# mr_radar_ferret_afe.net
KiCad netlist of a schematic drawn in EAGLE
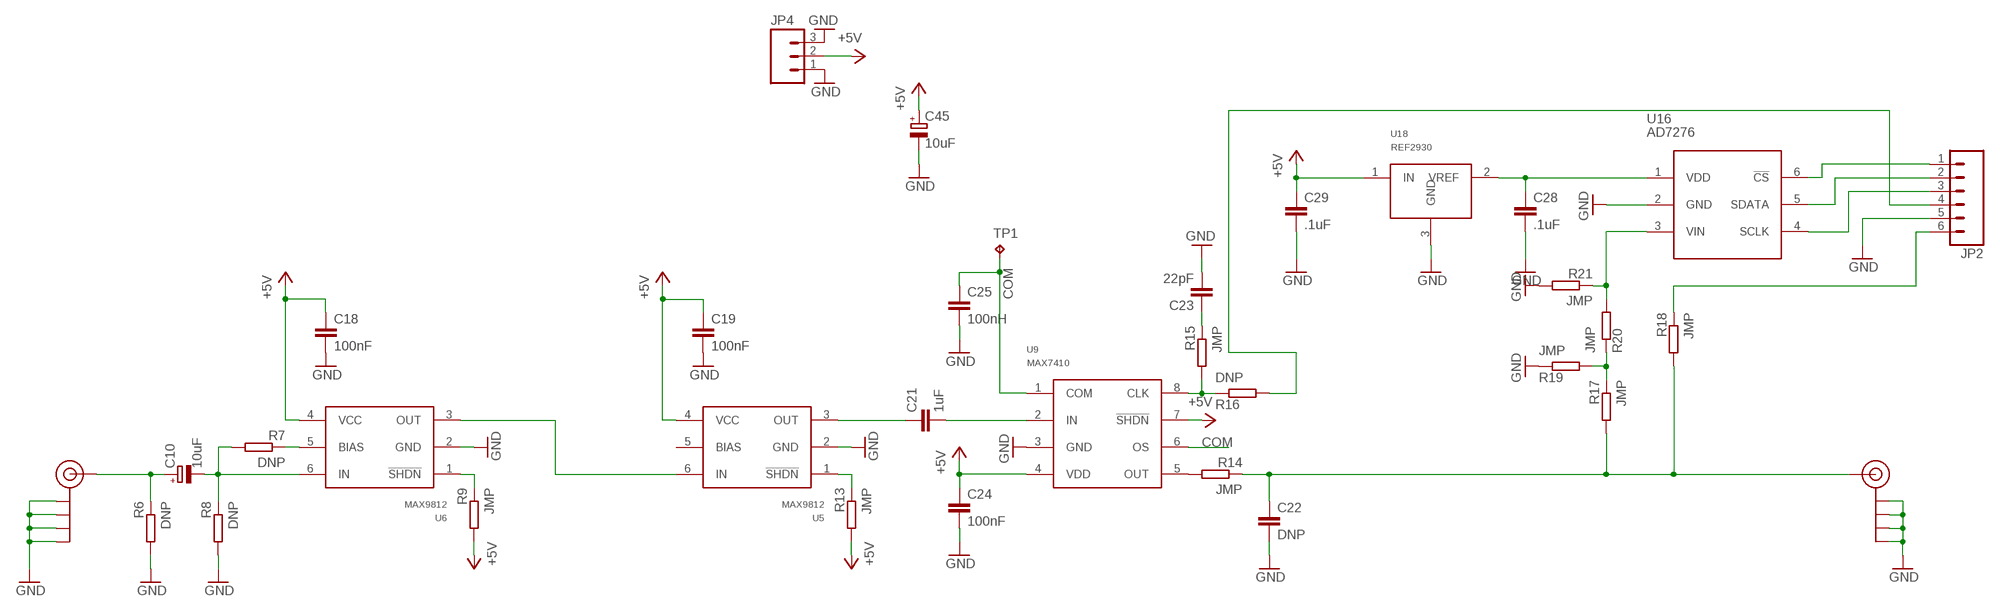
[diagram p0: schematic, sheet 1]

(export (version "E")
  (design (tool "Eeschema 10.0.6"))
  (components
    (comp (ref "C10")
      (value "10uF")
      (footprint "eagle-import:3216_A")
      (libsource (lib "eagle-import") (part "CAPACITOR-POLA"))
    )
    (comp (ref "C18")
      (value "100nF")
      (footprint "eagle-import:0603-CAP")
      (libsource (lib "eagle-import") (part "CAPACITOR-0603"))
    )
    (comp (ref "C19")
      (value "100nF")
      (footprint "eagle-import:0603-CAP")
      (libsource (lib "eagle-import") (part "CAPACITOR-0603"))
    )
    (comp (ref "C21")
      (value "1uF")
      (footprint "eagle-import:0603-CAP")
      (libsource (lib "eagle-import") (part "CAPACITOR-0603"))
    )
    (comp (ref "C22")
      (value "DNP")
      (footprint "eagle-import:0603-CAP")
      (libsource (lib "eagle-import") (part "CAPACITOR-0603"))
    )
    (comp (ref "C23")
      (value "22pF")
      (footprint "eagle-import:0603-CAP")
      (libsource (lib "eagle-import") (part "CAPACITOR-0603"))
    )
    (comp (ref "C24")
      (value "100nF")
      (footprint "eagle-import:0603-CAP")
      (libsource (lib "eagle-import") (part "CAPACITOR-0603"))
    )
    (comp (ref "C25")
      (value "100nH")
      (footprint "eagle-import:0603-CAP")
      (libsource (lib "eagle-import") (part "CAPACITOR-0603"))
    )
    (comp (ref "C28")
      (value ".1uF")
      (footprint "eagle-import:0603-CAP")
      (libsource (lib "eagle-import") (part "CAPACITOR-0603"))
    )
    (comp (ref "C29")
      (value ".1uF")
      (footprint "eagle-import:0603-CAP")
      (libsource (lib "eagle-import") (part "CAPACITOR-0603"))
    )
    (comp (ref "C45")
      (value "10uF")
      (footprint "eagle-import:3216_A")
      (libsource (lib "eagle-import") (part "CAPACITOR-POLA"))
    )
    (comp (ref "J$3")
      (value "SMA_EDGE")
      (footprint "eagle-import:SMA-EDGE")
      (libsource (lib "eagle-import") (part "SMA_EDGE"))
    )
    (comp (ref "J$6")
      (value "SMA_EDGE")
      (footprint "eagle-import:SMA-EDGE")
      (libsource (lib "eagle-import") (part "SMA_EDGE"))
    )
    (comp (ref "JP2")
      (value "M06SIP")
      (footprint "eagle-import:1X06")
      (libsource (lib "eagle-import") (part "M06SIP"))
    )
    (comp (ref "JP4")
      (value "M03SCREW")
      (footprint "eagle-import:SCREWTERMINAL-3.5MM-3")
      (libsource (lib "eagle-import") (part "M03SCREW"))
    )
    (comp (ref "R6")
      (value "DNP")
      (footprint "eagle-import:0603-RES")
      (libsource (lib "eagle-import") (part "RESISTOR-0603"))
    )
    (comp (ref "R7")
      (value "DNP")
      (footprint "eagle-import:0603-RES")
      (libsource (lib "eagle-import") (part "RESISTOR-0603"))
    )
    (comp (ref "R8")
      (value "DNP")
      (footprint "eagle-import:0603-RES")
      (libsource (lib "eagle-import") (part "RESISTOR-0603"))
    )
    (comp (ref "R9")
      (value "JMP")
      (footprint "eagle-import:0603-RES")
      (libsource (lib "eagle-import") (part "RESISTOR-0603"))
    )
    (comp (ref "R13")
      (value "JMP")
      (footprint "eagle-import:0603-RES")
      (libsource (lib "eagle-import") (part "RESISTOR-0603"))
    )
    (comp (ref "R14")
      (value "JMP")
      (footprint "eagle-import:0603-RES")
      (libsource (lib "eagle-import") (part "RESISTOR-0603"))
    )
    (comp (ref "R15")
      (value "JMP")
      (footprint "eagle-import:0603-RES")
      (libsource (lib "eagle-import") (part "RESISTOR-0603"))
    )
    (comp (ref "R16")
      (value "DNP")
      (footprint "eagle-import:0603-RES")
      (libsource (lib "eagle-import") (part "RESISTOR-0603"))
    )
    (comp (ref "R17")
      (value "JMP")
      (footprint "eagle-import:0603-RES")
      (libsource (lib "eagle-import") (part "RESISTOR-0603"))
    )
    (comp (ref "R18")
      (value "JMP")
      (footprint "eagle-import:0603-RES")
      (libsource (lib "eagle-import") (part "RESISTOR-0603"))
    )
    (comp (ref "R19")
      (value "JMP")
      (footprint "eagle-import:0603-RES")
      (libsource (lib "eagle-import") (part "RESISTOR-0603"))
    )
    (comp (ref "R20")
      (value "JMP")
      (footprint "eagle-import:0603-RES")
      (libsource (lib "eagle-import") (part "RESISTOR-0603"))
    )
    (comp (ref "R21")
      (value "JMP")
      (footprint "eagle-import:0603-RES")
      (libsource (lib "eagle-import") (part "RESISTOR-0603"))
    )
    (comp (ref "TP1")
      (value "TPTP14SQ")
      (footprint "eagle-import:TP14SQ")
      (libsource (lib "eagle-import") (part "TPTP14SQ"))
    )
    (comp (ref "U5")
      (value "MAX9812")
      (footprint "eagle-import:SC70-6")
      (libsource (lib "eagle-import") (part "MAX9812"))
    )
    (comp (ref "U6")
      (value "MAX9812")
      (footprint "eagle-import:SC70-6")
      (libsource (lib "eagle-import") (part "MAX9812"))
    )
    (comp (ref "U9")
      (value "MAX7410")
      (footprint "eagle-import:UMAX8")
      (libsource (lib "eagle-import") (part "MAX7410"))
    )
    (comp (ref "U16")
      (value "AD7276")
      (footprint "eagle-import:SOT23-6")
      (libsource (lib "eagle-import") (part "AD7276"))
    )
    (comp (ref "U18")
      (value "REF2930")
      (footprint "eagle-import:SOT23-3")
      (libsource (lib "eagle-import") (part "REF2930"))
    )
  )
  (nets
    (net (code "1") (name "+5V") (class "Default")
      (node (ref "C18") (pin "P$1") (pinfunction "1_P$1") (pintype "passive"))
      (node (ref "C19") (pin "P$1") (pinfunction "1_P$1") (pintype "passive"))
      (node (ref "C24") (pin "P$1") (pinfunction "1_P$1") (pintype "passive"))
      (node (ref "C29") (pin "P$1") (pinfunction "1_P$1") (pintype "passive"))
      (node (ref "C45") (pin "+") (pinfunction "+_+") (pintype "passive"))
      (node (ref "JP4") (pin "2") (pinfunction "2_2") (pintype "passive"))
      (node (ref "R13") (pin "P$2") (pinfunction "2_P$2") (pintype "passive"))
      (node (ref "R9") (pin "P$2") (pinfunction "2_P$2") (pintype "passive"))
      (node (ref "U18") (pin "1") (pinfunction "IN_1") (pintype "input"))
      (node (ref "U5") (pin "4") (pinfunction "VCC_4") (pintype "bidirectional"))
      (node (ref "U6") (pin "4") (pinfunction "VCC_4") (pintype "bidirectional"))
      (node (ref "U9") (pin "4") (pinfunction "VDD_4") (pintype "bidirectional"))
      (node (ref "U9") (pin "7") (pinfunction "~{SHDN}_7") (pintype "bidirectional"))
    )
    (net (code "2") (name "/COM") (class "Default")
      (node (ref "C25") (pin "P$1") (pinfunction "1_P$1") (pintype "passive"))
      (node (ref "TP1") (pin "TP") (pinfunction "TP_TP") (pintype "input"))
      (node (ref "U9") (pin "1") (pinfunction "COM_1") (pintype "bidirectional"))
      (node (ref "U9") (pin "6") (pinfunction "OS_6") (pintype "bidirectional"))
    )
    (net (code "3") (name "GND") (class "Default")
      (node (ref "C18") (pin "P$2") (pinfunction "2_P$2") (pintype "passive"))
      (node (ref "C19") (pin "P$2") (pinfunction "2_P$2") (pintype "passive"))
      (node (ref "C22") (pin "P$2") (pinfunction "2_P$2") (pintype "passive"))
      (node (ref "C23") (pin "P$2") (pinfunction "2_P$2") (pintype "passive"))
      (node (ref "C24") (pin "P$2") (pinfunction "2_P$2") (pintype "passive"))
      (node (ref "C25") (pin "P$2") (pinfunction "2_P$2") (pintype "passive"))
      (node (ref "C28") (pin "P$2") (pinfunction "2_P$2") (pintype "passive"))
      (node (ref "C29") (pin "P$2") (pinfunction "2_P$2") (pintype "passive"))
      (node (ref "C45") (pin "-") (pinfunction "-_-") (pintype "passive"))
      (node (ref "J$3") (pin "GND@0") (pinfunction "GND_GND@0") (pintype "bidirectional"))
      (node (ref "J$3") (pin "GND@1") (pinfunction "GND_GND@1") (pintype "bidirectional"))
      (node (ref "J$3") (pin "GND@2") (pinfunction "GND_GND@2") (pintype "bidirectional"))
      (node (ref "J$3") (pin "GND@3") (pinfunction "GND_GND@3") (pintype "bidirectional"))
      (node (ref "J$6") (pin "GND@0") (pinfunction "GND_GND@0") (pintype "bidirectional"))
      (node (ref "J$6") (pin "GND@1") (pinfunction "GND_GND@1") (pintype "bidirectional"))
      (node (ref "J$6") (pin "GND@2") (pinfunction "GND_GND@2") (pintype "bidirectional"))
      (node (ref "J$6") (pin "GND@3") (pinfunction "GND_GND@3") (pintype "bidirectional"))
      (node (ref "JP2") (pin "5") (pinfunction "5_5") (pintype "passive"))
      (node (ref "JP4") (pin "1") (pinfunction "1_1") (pintype "passive"))
      (node (ref "JP4") (pin "3") (pinfunction "3_3") (pintype "passive"))
      (node (ref "R19") (pin "P$1") (pinfunction "1_P$1") (pintype "passive"))
      (node (ref "R21") (pin "P$2") (pinfunction "2_P$2") (pintype "passive"))
      (node (ref "R6") (pin "P$2") (pinfunction "2_P$2") (pintype "passive"))
      (node (ref "R8") (pin "P$2") (pinfunction "2_P$2") (pintype "passive"))
      (node (ref "U16") (pin "2") (pinfunction "GND_2") (pintype "bidirectional"))
      (node (ref "U18") (pin "3") (pinfunction "GND_3") (pintype "bidirectional"))
      (node (ref "U5") (pin "2") (pinfunction "GND_2") (pintype "bidirectional"))
      (node (ref "U6") (pin "2") (pinfunction "GND_2") (pintype "bidirectional"))
      (node (ref "U9") (pin "3") (pinfunction "GND_3") (pintype "bidirectional"))
    )
    (net (code "4") (name "Net-(C21-1)") (class "Default")
      (node (ref "C21") (pin "P$1") (pinfunction "1_P$1") (pintype "passive"))
      (node (ref "U5") (pin "3") (pinfunction "OUT_3") (pintype "output"))
    )
    (net (code "5") (name "Net-(C21-2)") (class "Default")
      (node (ref "C21") (pin "P$2") (pinfunction "2_P$2") (pintype "passive"))
      (node (ref "U9") (pin "2") (pinfunction "IN_2") (pintype "bidirectional"))
    )
    (net (code "6") (name "Net-(C22-1)") (class "Default")
      (node (ref "C22") (pin "P$1") (pinfunction "1_P$1") (pintype "passive"))
      (node (ref "J$3") (pin "SIG") (pinfunction "SIGNAL_SIG") (pintype "bidirectional"))
      (node (ref "R14") (pin "P$1") (pinfunction "1_P$1") (pintype "passive"))
      (node (ref "R17") (pin "P$2") (pinfunction "2_P$2") (pintype "passive"))
      (node (ref "R18") (pin "P$2") (pinfunction "2_P$2") (pintype "passive"))
    )
    (net (code "7") (name "Net-(C23-1)") (class "Default")
      (node (ref "C23") (pin "P$1") (pinfunction "1_P$1") (pintype "passive"))
      (node (ref "R15") (pin "P$1") (pinfunction "1_P$1") (pintype "passive"))
    )
    (net (code "8") (name "Net-(C28-1)") (class "Default")
      (node (ref "C28") (pin "P$1") (pinfunction "1_P$1") (pintype "passive"))
      (node (ref "U16") (pin "1") (pinfunction "VDD_1") (pintype "bidirectional"))
      (node (ref "U18") (pin "2") (pinfunction "VREF_2") (pintype "bidirectional"))
    )
    (net (code "9") (name "Net-(J$6-SIGNAL)") (class "Default")
      (node (ref "C10") (pin "+") (pinfunction "+_+") (pintype "passive"))
      (node (ref "J$6") (pin "SIG") (pinfunction "SIGNAL_SIG") (pintype "bidirectional"))
      (node (ref "R6") (pin "P$1") (pinfunction "1_P$1") (pintype "passive"))
    )
    (net (code "10") (name "Net-(R7-1)") (class "Default")
      (node (ref "R7") (pin "P$1") (pinfunction "1_P$1") (pintype "passive"))
      (node (ref "U6") (pin "5") (pinfunction "BIAS_5") (pintype "output"))
    )
    (net (code "11") (name "Net-(R7-2)") (class "Default")
      (node (ref "C10") (pin "-") (pinfunction "-_-") (pintype "passive"))
      (node (ref "R7") (pin "P$2") (pinfunction "2_P$2") (pintype "passive"))
      (node (ref "R8") (pin "P$1") (pinfunction "1_P$1") (pintype "passive"))
      (node (ref "U6") (pin "6") (pinfunction "IN_6") (pintype "input"))
    )
    (net (code "12") (name "Net-(R9-1)") (class "Default")
      (node (ref "R9") (pin "P$1") (pinfunction "1_P$1") (pintype "passive"))
      (node (ref "U6") (pin "1") (pinfunction "~{SHDN}_1") (pintype "input"))
    )
    (net (code "13") (name "Net-(R13-1)") (class "Default")
      (node (ref "R13") (pin "P$1") (pinfunction "1_P$1") (pintype "passive"))
      (node (ref "U5") (pin "1") (pinfunction "~{SHDN}_1") (pintype "input"))
    )
    (net (code "14") (name "Net-(R14-2)") (class "Default")
      (node (ref "R14") (pin "P$2") (pinfunction "2_P$2") (pintype "passive"))
      (node (ref "U9") (pin "5") (pinfunction "OUT_5") (pintype "bidirectional"))
    )
    (net (code "15") (name "Net-(R15-2)") (class "Default")
      (node (ref "R15") (pin "P$2") (pinfunction "2_P$2") (pintype "passive"))
      (node (ref "R16") (pin "P$1") (pinfunction "1_P$1") (pintype "passive"))
      (node (ref "U9") (pin "8") (pinfunction "CLK_8") (pintype "bidirectional"))
    )
    (net (code "16") (name "Net-(R16-2)") (class "Default")
      (node (ref "JP2") (pin "4") (pinfunction "4_4") (pintype "passive"))
      (node (ref "R16") (pin "P$2") (pinfunction "2_P$2") (pintype "passive"))
    )
    (net (code "17") (name "Net-(R17-1)") (class "Default")
      (node (ref "R17") (pin "P$1") (pinfunction "1_P$1") (pintype "passive"))
      (node (ref "R19") (pin "P$2") (pinfunction "2_P$2") (pintype "passive"))
      (node (ref "R20") (pin "P$1") (pinfunction "1_P$1") (pintype "passive"))
    )
    (net (code "18") (name "Net-(R18-1)") (class "Default")
      (node (ref "JP2") (pin "6") (pinfunction "6_6") (pintype "passive"))
      (node (ref "R18") (pin "P$1") (pinfunction "1_P$1") (pintype "passive"))
    )
    (net (code "19") (name "Net-(R20-2)") (class "Default")
      (node (ref "R20") (pin "P$2") (pinfunction "2_P$2") (pintype "passive"))
      (node (ref "R21") (pin "P$1") (pinfunction "1_P$1") (pintype "passive"))
      (node (ref "U16") (pin "3") (pinfunction "VIN_3") (pintype "bidirectional"))
    )
    (net (code "20") (name "Net-(U5-IN)") (class "Default")
      (node (ref "U5") (pin "6") (pinfunction "IN_6") (pintype "input"))
      (node (ref "U6") (pin "3") (pinfunction "OUT_3") (pintype "output"))
    )
    (net (code "21") (name "Net-(U16-SCLK)") (class "Default")
      (node (ref "JP2") (pin "3") (pinfunction "3_3") (pintype "passive"))
      (node (ref "U16") (pin "4") (pinfunction "SCLK_4") (pintype "bidirectional"))
    )
    (net (code "22") (name "Net-(U16-SDATA)") (class "Default")
      (node (ref "JP2") (pin "2") (pinfunction "2_2") (pintype "passive"))
      (node (ref "U16") (pin "5") (pinfunction "SDATA_5") (pintype "bidirectional"))
    )
    (net (code "23") (name "Net-(U16-~{CS})") (class "Default")
      (node (ref "JP2") (pin "1") (pinfunction "1_1") (pintype "passive"))
      (node (ref "U16") (pin "6") (pinfunction "~{CS}_6") (pintype "bidirectional"))
    )
    (net (code "24") (name "unconnected-(U5-BIAS-Pad5)") (class "Default")
      (node (ref "U5") (pin "5") (pinfunction "BIAS_5") (pintype "output"))
    )
  )
)
